# untitled.net
KiCad netlist of a schematic drawn in EAGLE
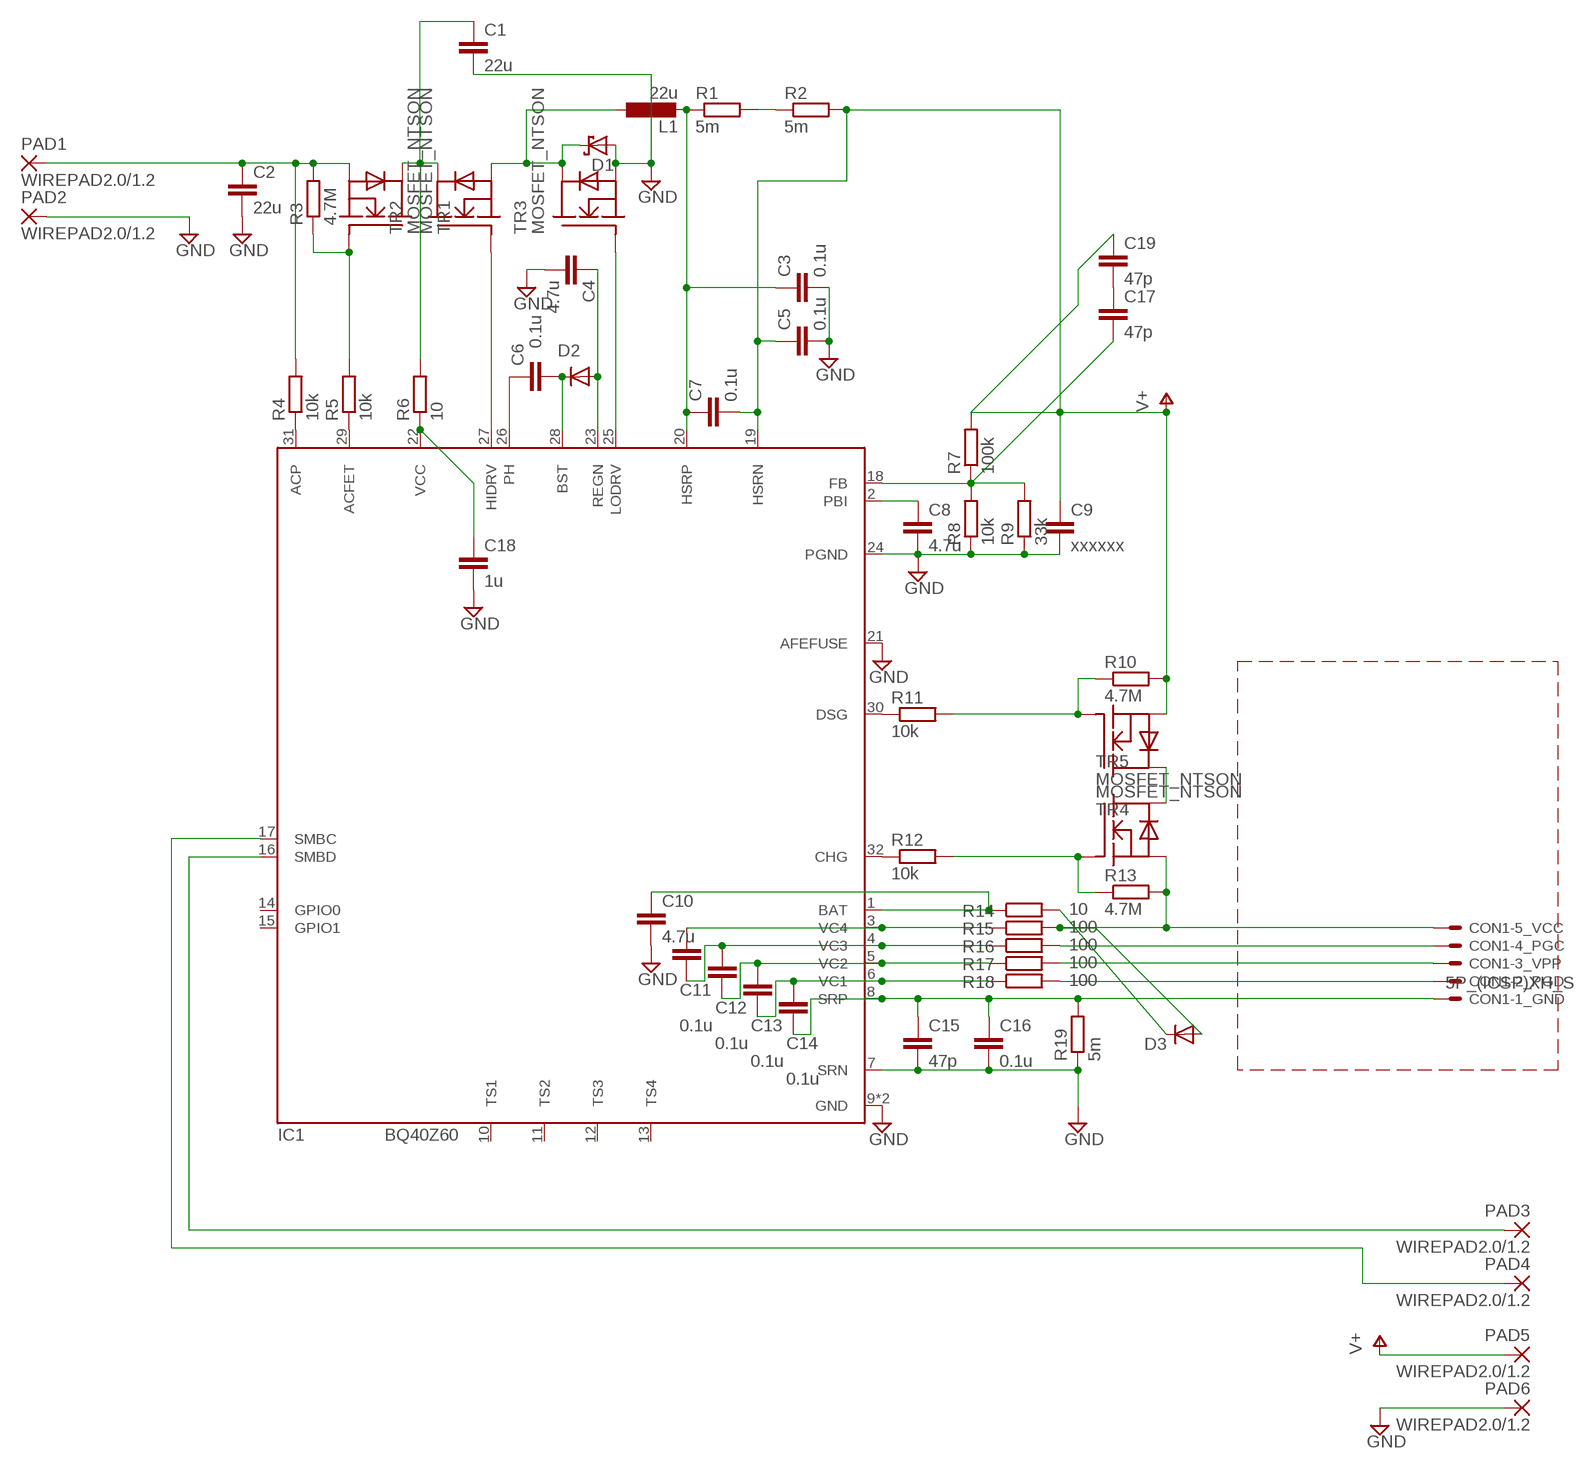
[diagram p0: schematic, sheet 1]

(export (version "E")
  (design (tool "Eeschema 10.0.6"))
  (components
    (comp (ref "C1")
      (value "22u")
      (footprint "eagle-import:C1210")
      (libsource (lib "eagle-import") (part "C-EUC1210"))
    )
    (comp (ref "C2")
      (value "22u")
      (footprint "eagle-import:C1210")
      (libsource (lib "eagle-import") (part "C-EUC1210"))
    )
    (comp (ref "C3")
      (value "0.1u")
      (footprint "eagle-import:C0402")
      (libsource (lib "eagle-import") (part "C-EUC0402"))
    )
    (comp (ref "C4")
      (value "4.7u")
      (footprint "eagle-import:C0402")
      (libsource (lib "eagle-import") (part "C-EUC0402"))
    )
    (comp (ref "C5")
      (value "0.1u")
      (footprint "eagle-import:C0402")
      (libsource (lib "eagle-import") (part "C-EUC0402"))
    )
    (comp (ref "C6")
      (value "0.1u")
      (footprint "eagle-import:C0402")
      (libsource (lib "eagle-import") (part "C-EUC0402"))
    )
    (comp (ref "C7")
      (value "0.1u")
      (footprint "eagle-import:C0402")
      (libsource (lib "eagle-import") (part "C-EUC0402"))
    )
    (comp (ref "C8")
      (value "4.7u")
      (footprint "eagle-import:C0805")
      (libsource (lib "eagle-import") (part "C-EUC0805"))
    )
    (comp (ref "C9")
      (value "xxxxxx")
      (footprint "eagle-import:C0402")
      (libsource (lib "eagle-import") (part "C-EUC0402"))
    )
    (comp (ref "C10")
      (value "4.7u")
      (footprint "eagle-import:C0805")
      (libsource (lib "eagle-import") (part "C-EUC0805"))
    )
    (comp (ref "C11")
      (value "0.1u")
      (footprint "eagle-import:C0402")
      (libsource (lib "eagle-import") (part "C-EUC0402"))
    )
    (comp (ref "C12")
      (value "0.1u")
      (footprint "eagle-import:C0402")
      (libsource (lib "eagle-import") (part "C-EUC0402"))
    )
    (comp (ref "C13")
      (value "0.1u")
      (footprint "eagle-import:C0402")
      (libsource (lib "eagle-import") (part "C-EUC0402"))
    )
    (comp (ref "C14")
      (value "0.1u")
      (footprint "eagle-import:C0402")
      (libsource (lib "eagle-import") (part "C-EUC0402"))
    )
    (comp (ref "C15")
      (value "47p")
      (footprint "eagle-import:C0402")
      (libsource (lib "eagle-import") (part "C-EUC0402"))
    )
    (comp (ref "C16")
      (value "0.1u")
      (footprint "eagle-import:C0402")
      (libsource (lib "eagle-import") (part "C-EUC0402"))
    )
    (comp (ref "C17")
      (value "47p")
      (footprint "eagle-import:C0402")
      (libsource (lib "eagle-import") (part "C-EUC0402"))
    )
    (comp (ref "C18")
      (value "1u")
      (footprint "eagle-import:C0402")
      (libsource (lib "eagle-import") (part "C-EUC0402"))
    )
    (comp (ref "C19")
      (value "47p")
      (footprint "eagle-import:C0402")
      (libsource (lib "eagle-import") (part "C-EUC0402"))
    )
    (comp (ref "CON1")
      (value "5P_(ICSP)XH_S")
      (footprint "eagle-import:XH-5_S")
      (libsource (lib "eagle-import") (part "5P_(ICSP)XH_S"))
    )
    (comp (ref "D1")
      (value "SCHOTTKY-DIODETO-277A")
      (footprint "eagle-import:TO-277A")
      (libsource (lib "eagle-import") (part "SCHOTTKY-DIODETO-277A"))
    )
    (comp (ref "D2")
      (value "DIODE-VMN2")
      (footprint "eagle-import:VMN2")
      (libsource (lib "eagle-import") (part "DIODE-VMN2"))
    )
    (comp (ref "D3")
      (value "DIODE-VMN2")
      (footprint "eagle-import:VMN2")
      (libsource (lib "eagle-import") (part "DIODE-VMN2"))
    )
    (comp (ref "IC1")
      (value "BQ40Z60")
      (footprint "eagle-import:QFN32")
      (libsource (lib "eagle-import") (part "BQ40Z60"))
    )
    (comp (ref "L1")
      (value "22u")
      (footprint "eagle-import:SCRH125")
      (libsource (lib "eagle-import") (part "L-EUSCRH125"))
    )
    (comp (ref "PAD1")
      (value "WIREPAD2.0/1.2")
      (footprint "eagle-import:2.0_1.3")
      (libsource (lib "eagle-import") (part "WIREPAD2.0/1.2"))
    )
    (comp (ref "PAD2")
      (value "WIREPAD2.0/1.2")
      (footprint "eagle-import:2.0_1.3")
      (libsource (lib "eagle-import") (part "WIREPAD2.0/1.2"))
    )
    (comp (ref "PAD3")
      (value "WIREPAD2.0/1.2")
      (footprint "eagle-import:2.0_1.3")
      (libsource (lib "eagle-import") (part "WIREPAD2.0/1.2"))
    )
    (comp (ref "PAD4")
      (value "WIREPAD2.0/1.2")
      (footprint "eagle-import:2.0_1.3")
      (libsource (lib "eagle-import") (part "WIREPAD2.0/1.2"))
    )
    (comp (ref "PAD5")
      (value "WIREPAD2.0/1.2")
      (footprint "eagle-import:2.0_1.3")
      (libsource (lib "eagle-import") (part "WIREPAD2.0/1.2"))
    )
    (comp (ref "PAD6")
      (value "WIREPAD2.0/1.2")
      (footprint "eagle-import:2.0_1.3")
      (libsource (lib "eagle-import") (part "WIREPAD2.0/1.2"))
    )
    (comp (ref "R1")
      (value "5m")
      (footprint "eagle-import:R1210")
      (libsource (lib "eagle-import") (part "R-EU_R1210"))
    )
    (comp (ref "R2")
      (value "5m")
      (footprint "eagle-import:R1210")
      (libsource (lib "eagle-import") (part "R-EU_R1210"))
    )
    (comp (ref "R3")
      (value "4.7M")
      (footprint "eagle-import:R0402")
      (libsource (lib "eagle-import") (part "R-EU_R0402"))
    )
    (comp (ref "R4")
      (value "10k")
      (footprint "eagle-import:R0402")
      (libsource (lib "eagle-import") (part "R-EU_R0402"))
    )
    (comp (ref "R5")
      (value "10k")
      (footprint "eagle-import:R0402")
      (libsource (lib "eagle-import") (part "R-EU_R0402"))
    )
    (comp (ref "R6")
      (value "10")
      (footprint "eagle-import:R0402")
      (libsource (lib "eagle-import") (part "R-EU_R0402"))
    )
    (comp (ref "R7")
      (value "100k")
      (footprint "eagle-import:R0402")
      (libsource (lib "eagle-import") (part "R-EU_R0402"))
    )
    (comp (ref "R8")
      (value "10k")
      (footprint "eagle-import:R0402")
      (libsource (lib "eagle-import") (part "R-EU_R0402"))
    )
    (comp (ref "R9")
      (value "33k")
      (footprint "eagle-import:R0402")
      (libsource (lib "eagle-import") (part "R-EU_R0402"))
    )
    (comp (ref "R10")
      (value "4.7M")
      (footprint "eagle-import:R0402")
      (libsource (lib "eagle-import") (part "R-EU_R0402"))
    )
    (comp (ref "R11")
      (value "10k")
      (footprint "eagle-import:R0402")
      (libsource (lib "eagle-import") (part "R-EU_R0402"))
    )
    (comp (ref "R12")
      (value "10k")
      (footprint "eagle-import:R0402")
      (libsource (lib "eagle-import") (part "R-EU_R0402"))
    )
    (comp (ref "R13")
      (value "4.7M")
      (footprint "eagle-import:R0402")
      (libsource (lib "eagle-import") (part "R-EU_R0402"))
    )
    (comp (ref "R14")
      (value "10")
      (footprint "eagle-import:R0402")
      (libsource (lib "eagle-import") (part "R-EU_R0402"))
    )
    (comp (ref "R15")
      (value "100")
      (footprint "eagle-import:R0402")
      (libsource (lib "eagle-import") (part "R-EU_R0402"))
    )
    (comp (ref "R16")
      (value "100")
      (footprint "eagle-import:R0402")
      (libsource (lib "eagle-import") (part "R-EU_R0402"))
    )
    (comp (ref "R17")
      (value "100")
      (footprint "eagle-import:R0402")
      (libsource (lib "eagle-import") (part "R-EU_R0402"))
    )
    (comp (ref "R18")
      (value "100")
      (footprint "eagle-import:R0402")
      (libsource (lib "eagle-import") (part "R-EU_R0402"))
    )
    (comp (ref "R19")
      (value "5m")
      (footprint "eagle-import:R1210")
      (libsource (lib "eagle-import") (part "R-EU_R1210"))
    )
    (comp (ref "TR1")
      (value "MOSFET_NTSON")
      (footprint "eagle-import:TSON_ADVANCE")
      (libsource (lib "eagle-import") (part "MOSFET_NTSON"))
    )
    (comp (ref "TR2")
      (value "MOSFET_NTSON")
      (footprint "eagle-import:TSON_ADVANCE")
      (libsource (lib "eagle-import") (part "MOSFET_NTSON"))
    )
    (comp (ref "TR3")
      (value "MOSFET_NTSON")
      (footprint "eagle-import:TSON_ADVANCE")
      (libsource (lib "eagle-import") (part "MOSFET_NTSON"))
    )
    (comp (ref "TR4")
      (value "MOSFET_NTSON")
      (footprint "eagle-import:TSON_ADVANCE")
      (libsource (lib "eagle-import") (part "MOSFET_NTSON"))
    )
    (comp (ref "TR5")
      (value "MOSFET_NTSON")
      (footprint "eagle-import:TSON_ADVANCE")
      (libsource (lib "eagle-import") (part "MOSFET_NTSON"))
    )
  )
  (nets
    (net (code "1") (name "GND") (class "Default")
      (node (ref "C1") (pin "2") (pinfunction "2_2") (pintype "passive"))
      (node (ref "C10") (pin "2") (pinfunction "2_2") (pintype "passive"))
      (node (ref "C15") (pin "2") (pinfunction "2_2") (pintype "passive"))
      (node (ref "C16") (pin "2") (pinfunction "2_2") (pintype "passive"))
      (node (ref "C18") (pin "2") (pinfunction "2_2") (pintype "passive"))
      (node (ref "C2") (pin "2") (pinfunction "2_2") (pintype "passive"))
      (node (ref "C3") (pin "2") (pinfunction "2_2") (pintype "passive"))
      (node (ref "C4") (pin "2") (pinfunction "2_2") (pintype "passive"))
      (node (ref "C5") (pin "2") (pinfunction "2_2") (pintype "passive"))
      (node (ref "C8") (pin "2") (pinfunction "2_2") (pintype "passive"))
      (node (ref "C9") (pin "2") (pinfunction "2_2") (pintype "passive"))
      (node (ref "D1") (pin "A") (pinfunction "A_A") (pintype "passive"))
      (node (ref "IC1") (pin "21") (pinfunction "AFEFUSE_21") (pintype "output"))
      (node (ref "IC1") (pin "24") (pinfunction "PGND_24") (pintype "power_in"))
      (node (ref "IC1") (pin "7") (pinfunction "SRN_7") (pintype "input"))
      (node (ref "IC1") (pin "9") (pinfunction "GND_9") (pintype "power_in"))
      (node (ref "IC1") (pin "EXP") (pinfunction "GND_EXP") (pintype "power_in"))
      (node (ref "PAD2") (pin "1") (pinfunction "P_1") (pintype "passive"))
      (node (ref "PAD6") (pin "1") (pinfunction "P_1") (pintype "passive"))
      (node (ref "R19") (pin "1") (pinfunction "1_1") (pintype "passive"))
      (node (ref "R8") (pin "1") (pinfunction "1_1") (pintype "passive"))
      (node (ref "R9") (pin "1") (pinfunction "1_1") (pintype "passive"))
      (node (ref "TR3") (pin "1") (pinfunction "S_1") (pintype "bidirectional"))
      (node (ref "TR3") (pin "2") (pinfunction "S_2") (pintype "bidirectional"))
      (node (ref "TR3") (pin "3") (pinfunction "S_3") (pintype "bidirectional"))
    )
    (net (code "2") (name "Net-(C1-Pad1)") (class "Default")
      (node (ref "C1") (pin "1") (pinfunction "1_1") (pintype "passive"))
      (node (ref "R6") (pin "2") (pinfunction "2_2") (pintype "passive"))
      (node (ref "TR1") (pin "5") (pinfunction "D_5") (pintype "bidirectional"))
      (node (ref "TR1") (pin "6") (pinfunction "D_6") (pintype "bidirectional"))
      (node (ref "TR1") (pin "7") (pinfunction "D_7") (pintype "bidirectional"))
      (node (ref "TR1") (pin "8") (pinfunction "D_8") (pintype "bidirectional"))
      (node (ref "TR1") (pin "DRAIN1") (pinfunction "D_DRAIN1") (pintype "bidirectional"))
      (node (ref "TR1") (pin "DRAIN2") (pinfunction "D_DRAIN2") (pintype "bidirectional"))
      (node (ref "TR2") (pin "5") (pinfunction "D_5") (pintype "bidirectional"))
      (node (ref "TR2") (pin "6") (pinfunction "D_6") (pintype "bidirectional"))
      (node (ref "TR2") (pin "7") (pinfunction "D_7") (pintype "bidirectional"))
      (node (ref "TR2") (pin "8") (pinfunction "D_8") (pintype "bidirectional"))
      (node (ref "TR2") (pin "DRAIN1") (pinfunction "D_DRAIN1") (pintype "bidirectional"))
      (node (ref "TR2") (pin "DRAIN2") (pinfunction "D_DRAIN2") (pintype "bidirectional"))
    )
    (net (code "3") (name "Net-(C17-Pad1)") (class "Default")
      (node (ref "C17") (pin "1") (pinfunction "1_1") (pintype "passive"))
      (node (ref "C19") (pin "2") (pinfunction "2_2") (pintype "passive"))
    )
    (net (code "4") (name "Net-(CON1A-S)") (class "Default")
      (node (ref "C14") (pin "2") (pinfunction "2_2") (pintype "passive"))
      (node (ref "C15") (pin "1") (pinfunction "1_1") (pintype "passive"))
      (node (ref "C16") (pin "1") (pinfunction "1_1") (pintype "passive"))
      (node (ref "CON1") (pin "5") (pinfunction "S_5") (pintype "passive"))
      (node (ref "IC1") (pin "8") (pinfunction "SRP_8") (pintype "input"))
      (node (ref "R19") (pin "2") (pinfunction "2_2") (pintype "passive"))
    )
    (net (code "5") (name "Net-(CON1B-S)") (class "Default")
      (node (ref "CON1") (pin "4") (pinfunction "S_4") (pintype "passive"))
      (node (ref "R18") (pin "2") (pinfunction "2_2") (pintype "passive"))
    )
    (net (code "6") (name "Net-(CON1C-S)") (class "Default")
      (node (ref "CON1") (pin "3") (pinfunction "S_3") (pintype "passive"))
      (node (ref "R17") (pin "2") (pinfunction "2_2") (pintype "passive"))
    )
    (net (code "7") (name "Net-(CON1D-S)") (class "Default")
      (node (ref "CON1") (pin "2") (pinfunction "S_2") (pintype "passive"))
      (node (ref "R16") (pin "2") (pinfunction "2_2") (pintype "passive"))
    )
    (net (code "8") (name "Net-(CON1E-S)") (class "Default")
      (node (ref "CON1") (pin "1") (pinfunction "S_1") (pintype "passive"))
      (node (ref "D3") (pin "A") (pinfunction "A_A") (pintype "passive"))
      (node (ref "R13") (pin "2") (pinfunction "2_2") (pintype "passive"))
      (node (ref "R15") (pin "2") (pinfunction "2_2") (pintype "passive"))
      (node (ref "TR5") (pin "1") (pinfunction "S_1") (pintype "bidirectional"))
      (node (ref "TR5") (pin "2") (pinfunction "S_2") (pintype "bidirectional"))
      (node (ref "TR5") (pin "3") (pinfunction "S_3") (pintype "bidirectional"))
    )
    (net (code "9") (name "Net-(D1-PadC)") (class "Default")
      (node (ref "D1") (pin "C") (pinfunction "C_C") (pintype "passive"))
      (node (ref "L1") (pin "1") (pinfunction "1_1") (pintype "passive"))
      (node (ref "TR2") (pin "1") (pinfunction "S_1") (pintype "bidirectional"))
      (node (ref "TR2") (pin "2") (pinfunction "S_2") (pintype "bidirectional"))
      (node (ref "TR2") (pin "3") (pinfunction "S_3") (pintype "bidirectional"))
      (node (ref "TR3") (pin "5") (pinfunction "D_5") (pintype "bidirectional"))
      (node (ref "TR3") (pin "6") (pinfunction "D_6") (pintype "bidirectional"))
      (node (ref "TR3") (pin "7") (pinfunction "D_7") (pintype "bidirectional"))
      (node (ref "TR3") (pin "8") (pinfunction "D_8") (pintype "bidirectional"))
      (node (ref "TR3") (pin "DRAIN1") (pinfunction "D_DRAIN1") (pintype "bidirectional"))
      (node (ref "TR3") (pin "DRAIN2") (pinfunction "D_DRAIN2") (pintype "bidirectional"))
    )
    (net (code "10") (name "Net-(D3-PadC)") (class "Default")
      (node (ref "D3") (pin "C") (pinfunction "C_C") (pintype "passive"))
      (node (ref "R14") (pin "2") (pinfunction "2_2") (pintype "passive"))
    )
    (net (code "11") (name "Net-(IC1-ACFET)") (class "Default")
      (node (ref "IC1") (pin "29") (pinfunction "ACFET_29") (pintype "output"))
      (node (ref "R5") (pin "1") (pinfunction "1_1") (pintype "passive"))
    )
    (net (code "12") (name "Net-(IC1-ACP)") (class "Default")
      (node (ref "IC1") (pin "31") (pinfunction "ACP_31") (pintype "input"))
      (node (ref "R4") (pin "1") (pinfunction "1_1") (pintype "passive"))
    )
    (net (code "13") (name "Net-(IC1-BAT)") (class "Default")
      (node (ref "C10") (pin "1") (pinfunction "1_1") (pintype "passive"))
      (node (ref "IC1") (pin "1") (pinfunction "BAT_1") (pintype "power_in"))
      (node (ref "R14") (pin "1") (pinfunction "1_1") (pintype "passive"))
    )
    (net (code "14") (name "Net-(IC1-BST)") (class "Default")
      (node (ref "C6") (pin "2") (pinfunction "2_2") (pintype "passive"))
      (node (ref "D2") (pin "C") (pinfunction "C_C") (pintype "passive"))
      (node (ref "IC1") (pin "28") (pinfunction "BST_28") (pintype "input"))
    )
    (net (code "15") (name "Net-(IC1-CHG)") (class "Default")
      (node (ref "IC1") (pin "32") (pinfunction "CHG_32") (pintype "output"))
      (node (ref "R12") (pin "1") (pinfunction "1_1") (pintype "passive"))
    )
    (net (code "16") (name "Net-(IC1-DSG)") (class "Default")
      (node (ref "IC1") (pin "30") (pinfunction "DSG_30") (pintype "output"))
      (node (ref "R11") (pin "1") (pinfunction "1_1") (pintype "passive"))
    )
    (net (code "17") (name "Net-(IC1-FB)") (class "Default")
      (node (ref "C17") (pin "2") (pinfunction "2_2") (pintype "passive"))
      (node (ref "IC1") (pin "18") (pinfunction "FB_18") (pintype "input"))
      (node (ref "R7") (pin "1") (pinfunction "1_1") (pintype "passive"))
      (node (ref "R8") (pin "2") (pinfunction "2_2") (pintype "passive"))
      (node (ref "R9") (pin "2") (pinfunction "2_2") (pintype "passive"))
    )
    (net (code "18") (name "Net-(IC1-HIDRV)") (class "Default")
      (node (ref "IC1") (pin "27") (pinfunction "HIDRV_27") (pintype "output"))
      (node (ref "TR2") (pin "4") (pinfunction "G_4") (pintype "bidirectional"))
    )
    (net (code "19") (name "Net-(IC1-HSRP)") (class "Default")
      (node (ref "C3") (pin "1") (pinfunction "1_1") (pintype "passive"))
      (node (ref "C7") (pin "1") (pinfunction "1_1") (pintype "passive"))
      (node (ref "IC1") (pin "20") (pinfunction "HSRP_20") (pintype "input"))
      (node (ref "L1") (pin "2") (pinfunction "2_2") (pintype "passive"))
      (node (ref "R1") (pin "1") (pinfunction "1_1") (pintype "passive"))
    )
    (net (code "20") (name "Net-(IC1-LODRV)") (class "Default")
      (node (ref "IC1") (pin "25") (pinfunction "LODRV_25") (pintype "output"))
      (node (ref "TR3") (pin "4") (pinfunction "G_4") (pintype "bidirectional"))
    )
    (net (code "21") (name "Net-(IC1-PBI)") (class "Default")
      (node (ref "C8") (pin "1") (pinfunction "1_1") (pintype "passive"))
      (node (ref "IC1") (pin "2") (pinfunction "PBI_2") (pintype "power_in"))
    )
    (net (code "22") (name "Net-(IC1-PH)") (class "Default")
      (node (ref "C6") (pin "1") (pinfunction "1_1") (pintype "passive"))
      (node (ref "IC1") (pin "26") (pinfunction "PH_26") (pintype "bidirectional"))
    )
    (net (code "23") (name "Net-(IC1-REGN)") (class "Default")
      (node (ref "C4") (pin "1") (pinfunction "1_1") (pintype "passive"))
      (node (ref "D2") (pin "A") (pinfunction "A_A") (pintype "passive"))
      (node (ref "IC1") (pin "23") (pinfunction "REGN_23") (pintype "output"))
    )
    (net (code "24") (name "Net-(IC1-SMBC)") (class "Default")
      (node (ref "IC1") (pin "17") (pinfunction "SMBC_17") (pintype "bidirectional"))
      (node (ref "PAD4") (pin "1") (pinfunction "P_1") (pintype "passive"))
    )
    (net (code "25") (name "Net-(IC1-SMBD)") (class "Default")
      (node (ref "IC1") (pin "16") (pinfunction "SMBD_16") (pintype "bidirectional"))
      (node (ref "PAD3") (pin "1") (pinfunction "P_1") (pintype "passive"))
    )
    (net (code "26") (name "Net-(IC1-VC1)") (class "Default")
      (node (ref "C13") (pin "2") (pinfunction "2_2") (pintype "passive"))
      (node (ref "C14") (pin "1") (pinfunction "1_1") (pintype "passive"))
      (node (ref "IC1") (pin "6") (pinfunction "VC1_6") (pintype "input"))
      (node (ref "R18") (pin "1") (pinfunction "1_1") (pintype "passive"))
    )
    (net (code "27") (name "Net-(IC1-VC2)") (class "Default")
      (node (ref "C12") (pin "2") (pinfunction "2_2") (pintype "passive"))
      (node (ref "C13") (pin "1") (pinfunction "1_1") (pintype "passive"))
      (node (ref "IC1") (pin "5") (pinfunction "VC2_5") (pintype "input"))
      (node (ref "R17") (pin "1") (pinfunction "1_1") (pintype "passive"))
    )
    (net (code "28") (name "Net-(IC1-VC3)") (class "Default")
      (node (ref "C11") (pin "2") (pinfunction "2_2") (pintype "passive"))
      (node (ref "C12") (pin "1") (pinfunction "1_1") (pintype "passive"))
      (node (ref "IC1") (pin "4") (pinfunction "VC3_4") (pintype "input"))
      (node (ref "R16") (pin "1") (pinfunction "1_1") (pintype "passive"))
    )
    (net (code "29") (name "Net-(IC1-VC4)") (class "Default")
      (node (ref "C11") (pin "1") (pinfunction "1_1") (pintype "passive"))
      (node (ref "IC1") (pin "3") (pinfunction "VC4_3") (pintype "input"))
      (node (ref "R15") (pin "1") (pinfunction "1_1") (pintype "passive"))
    )
    (net (code "30") (name "Net-(IC1-VCC)") (class "Default")
      (node (ref "C18") (pin "1") (pinfunction "1_1") (pintype "passive"))
      (node (ref "IC1") (pin "22") (pinfunction "VCC_22") (pintype "power_in"))
      (node (ref "R6") (pin "1") (pinfunction "1_1") (pintype "passive"))
    )
    (net (code "31") (name "Net-(PAD1-P)") (class "Default")
      (node (ref "C2") (pin "1") (pinfunction "1_1") (pintype "passive"))
      (node (ref "PAD1") (pin "1") (pinfunction "P_1") (pintype "passive"))
      (node (ref "R3") (pin "2") (pinfunction "2_2") (pintype "passive"))
      (node (ref "R4") (pin "2") (pinfunction "2_2") (pintype "passive"))
      (node (ref "TR1") (pin "1") (pinfunction "S_1") (pintype "bidirectional"))
      (node (ref "TR1") (pin "2") (pinfunction "S_2") (pintype "bidirectional"))
      (node (ref "TR1") (pin "3") (pinfunction "S_3") (pintype "bidirectional"))
    )
    (net (code "32") (name "Net-(R1-Pad2)") (class "Default")
      (node (ref "R1") (pin "2") (pinfunction "2_2") (pintype "passive"))
      (node (ref "R2") (pin "1") (pinfunction "1_1") (pintype "passive"))
    )
    (net (code "33") (name "Net-(TR1-G)") (class "Default")
      (node (ref "R3") (pin "1") (pinfunction "1_1") (pintype "passive"))
      (node (ref "R5") (pin "2") (pinfunction "2_2") (pintype "passive"))
      (node (ref "TR1") (pin "4") (pinfunction "G_4") (pintype "bidirectional"))
    )
    (net (code "34") (name "Net-(TR4-D-Pad5)") (class "Default")
      (node (ref "TR4") (pin "5") (pinfunction "D_5") (pintype "bidirectional"))
      (node (ref "TR4") (pin "6") (pinfunction "D_6") (pintype "bidirectional"))
      (node (ref "TR4") (pin "7") (pinfunction "D_7") (pintype "bidirectional"))
      (node (ref "TR4") (pin "8") (pinfunction "D_8") (pintype "bidirectional"))
      (node (ref "TR4") (pin "DRAIN1") (pinfunction "D_DRAIN1") (pintype "bidirectional"))
      (node (ref "TR4") (pin "DRAIN2") (pinfunction "D_DRAIN2") (pintype "bidirectional"))
      (node (ref "TR5") (pin "5") (pinfunction "D_5") (pintype "bidirectional"))
      (node (ref "TR5") (pin "6") (pinfunction "D_6") (pintype "bidirectional"))
      (node (ref "TR5") (pin "7") (pinfunction "D_7") (pintype "bidirectional"))
      (node (ref "TR5") (pin "8") (pinfunction "D_8") (pintype "bidirectional"))
      (node (ref "TR5") (pin "DRAIN1") (pinfunction "D_DRAIN1") (pintype "bidirectional"))
      (node (ref "TR5") (pin "DRAIN2") (pinfunction "D_DRAIN2") (pintype "bidirectional"))
    )
    (net (code "35") (name "Net-(TR4-G)") (class "Default")
      (node (ref "R10") (pin "1") (pinfunction "1_1") (pintype "passive"))
      (node (ref "R11") (pin "2") (pinfunction "2_2") (pintype "passive"))
      (node (ref "TR4") (pin "4") (pinfunction "G_4") (pintype "bidirectional"))
    )
    (net (code "36") (name "Net-(TR5-G)") (class "Default")
      (node (ref "R12") (pin "2") (pinfunction "2_2") (pintype "passive"))
      (node (ref "R13") (pin "1") (pinfunction "1_1") (pintype "passive"))
      (node (ref "TR5") (pin "4") (pinfunction "G_4") (pintype "bidirectional"))
    )
    (net (code "37") (name "V+") (class "Default")
      (node (ref "C19") (pin "1") (pinfunction "1_1") (pintype "passive"))
      (node (ref "C5") (pin "1") (pinfunction "1_1") (pintype "passive"))
      (node (ref "C7") (pin "2") (pinfunction "2_2") (pintype "passive"))
      (node (ref "C9") (pin "1") (pinfunction "1_1") (pintype "passive"))
      (node (ref "IC1") (pin "19") (pinfunction "HSRN_19") (pintype "input"))
      (node (ref "PAD5") (pin "1") (pinfunction "P_1") (pintype "passive"))
      (node (ref "R10") (pin "2") (pinfunction "2_2") (pintype "passive"))
      (node (ref "R2") (pin "2") (pinfunction "2_2") (pintype "passive"))
      (node (ref "R7") (pin "2") (pinfunction "2_2") (pintype "passive"))
      (node (ref "TR4") (pin "1") (pinfunction "S_1") (pintype "bidirectional"))
      (node (ref "TR4") (pin "2") (pinfunction "S_2") (pintype "bidirectional"))
      (node (ref "TR4") (pin "3") (pinfunction "S_3") (pintype "bidirectional"))
    )
    (net (code "38") (name "unconnected-(IC1-GPIO0-Pad14)") (class "Default")
      (node (ref "IC1") (pin "14") (pinfunction "GPIO0_14") (pintype "bidirectional"))
    )
    (net (code "39") (name "unconnected-(IC1-GPIO1-Pad15)") (class "Default")
      (node (ref "IC1") (pin "15") (pinfunction "GPIO1_15") (pintype "bidirectional"))
    )
    (net (code "40") (name "unconnected-(IC1-TS1-Pad10)") (class "Default")
      (node (ref "IC1") (pin "10") (pinfunction "TS1_10") (pintype "input"))
    )
    (net (code "41") (name "unconnected-(IC1-TS2-Pad11)") (class "Default")
      (node (ref "IC1") (pin "11") (pinfunction "TS2_11") (pintype "input"))
    )
    (net (code "42") (name "unconnected-(IC1-TS3-Pad12)") (class "Default")
      (node (ref "IC1") (pin "12") (pinfunction "TS3_12") (pintype "input"))
    )
    (net (code "43") (name "unconnected-(IC1-TS4-Pad13)") (class "Default")
      (node (ref "IC1") (pin "13") (pinfunction "TS4_13") (pintype "input"))
    )
  )
)
